# basic-handheld-turbidimeter.net
KiCad netlist of a schematic drawn in EAGLE
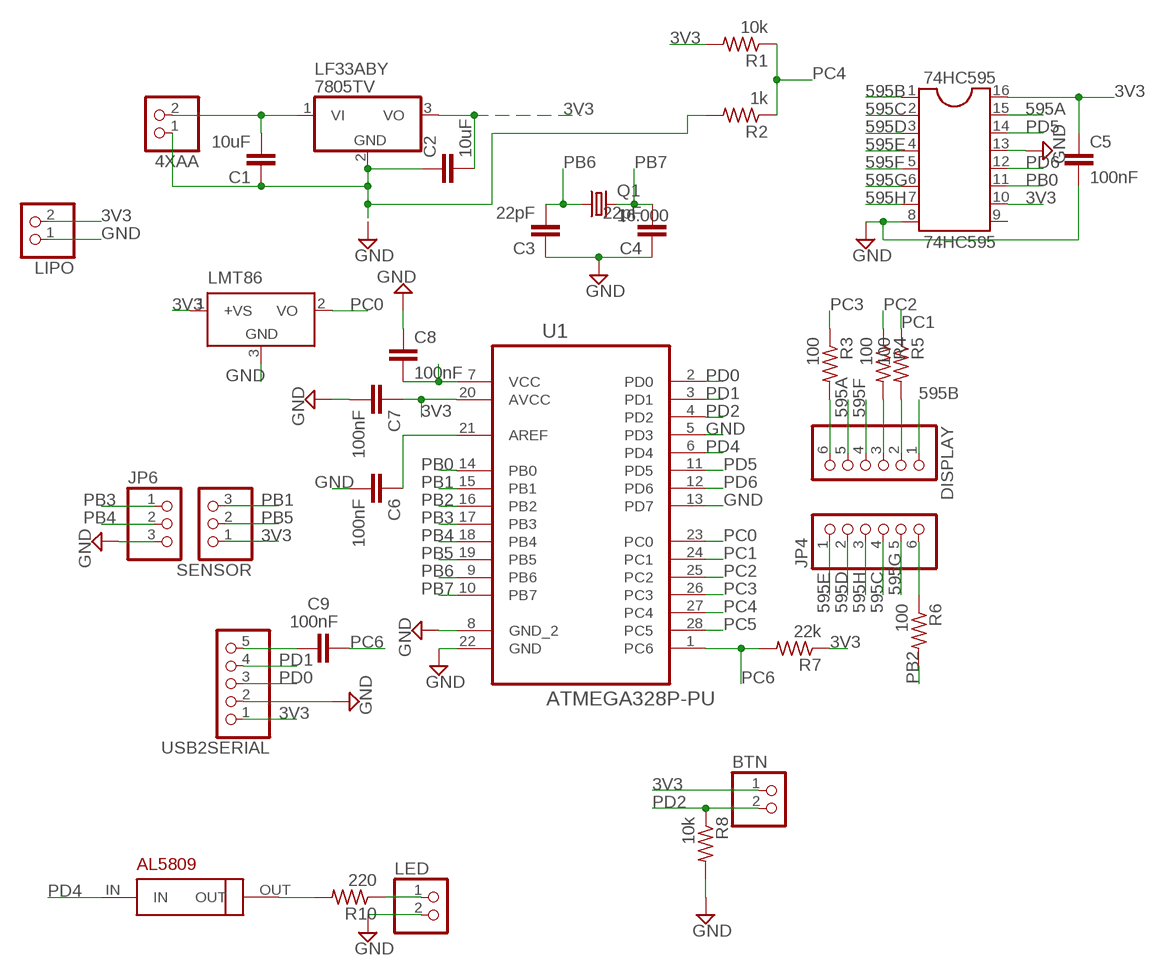
[diagram p0: schematic, sheet 1]

(export (version "E")
  (design (tool "Eeschema 10.0.6"))
  (components
    (comp (ref "4XAA")
      (value "PINHD-1X2")
      (footprint "eagle-import:1X02")
      (libsource (lib "eagle-import") (part "PINHD-1X2"))
    )
    (comp (ref "74HC595")
      (value "74HC595")
      (footprint "eagle-import:DIL16")
      (libsource (lib "eagle-import") (part "DIL16"))
    )
    (comp (ref "BTN")
      (value "PINHD-1X2")
      (footprint "eagle-import:1X02")
      (libsource (lib "eagle-import") (part "PINHD-1X2"))
    )
    (comp (ref "C1")
      (value "10uF")
      (footprint "eagle-import:CAP-PTH-SMALLEZ")
      (libsource (lib "eagle-import") (part "CAPEZ"))
    )
    (comp (ref "C2")
      (value "10uF")
      (footprint "eagle-import:CAP-PTH-SMALLEZ")
      (libsource (lib "eagle-import") (part "CAPEZ"))
    )
    (comp (ref "C3")
      (value "22pF")
      (footprint "eagle-import:CAP-PTH-SMALLEZ")
      (libsource (lib "eagle-import") (part "CAPEZ"))
    )
    (comp (ref "C4")
      (value "22pF")
      (footprint "eagle-import:CAP-PTH-SMALLEZ")
      (libsource (lib "eagle-import") (part "CAPEZ"))
    )
    (comp (ref "C5")
      (value "100nF")
      (footprint "eagle-import:CAP-PTH-SMALLEZ")
      (libsource (lib "eagle-import") (part "CAPEZ"))
    )
    (comp (ref "C6")
      (value "100nF")
      (footprint "eagle-import:CAP-PTH-SMALLEZ")
      (libsource (lib "eagle-import") (part "CAPEZ"))
    )
    (comp (ref "C7")
      (value "100nF")
      (footprint "eagle-import:CAP-PTH-SMALLEZ")
      (libsource (lib "eagle-import") (part "CAPEZ"))
    )
    (comp (ref "C8")
      (value "100nF")
      (footprint "eagle-import:CAP-PTH-SMALLEZ")
      (libsource (lib "eagle-import") (part "CAPEZ"))
    )
    (comp (ref "C9")
      (value "100nF")
      (footprint "eagle-import:CAP-PTH-SMALLEZ")
      (libsource (lib "eagle-import") (part "CAPEZ"))
    )
    (comp (ref "DISPLAY")
      (value "PINHD-1X6")
      (footprint "eagle-import:1X06")
      (libsource (lib "eagle-import") (part "PINHD-1X6"))
    )
    (comp (ref "JP4")
      (value "PINHD-1X6")
      (footprint "eagle-import:1X06")
      (libsource (lib "eagle-import") (part "PINHD-1X6"))
    )
    (comp (ref "JP6")
      (value "PINHD-1X3")
      (footprint "eagle-import:1X03")
      (libsource (lib "eagle-import") (part "PINHD-1X3"))
    )
    (comp (ref "LED")
      (value "PINHD-1X2")
      (footprint "eagle-import:1X02")
      (libsource (lib "eagle-import") (part "PINHD-1X2"))
    )
    (comp (ref "LF33ABY")
      (value "7805TV")
      (footprint "eagle-import:TO220V")
      (libsource (lib "eagle-import") (part "78TV05"))
    )
    (comp (ref "LIPO")
      (value "PINHD-1X2")
      (footprint "eagle-import:1X02")
      (libsource (lib "eagle-import") (part "PINHD-1X2"))
    )
    (comp (ref "LMT86")
      (value "LM35CZ")
      (footprint "eagle-import:TO92")
      (libsource (lib "eagle-import") (part "LM35CZ"))
    )
    (comp (ref "Q1")
      (value "16.000")
      (footprint "eagle-import:HC49_S")
      (libsource (lib "eagle-import") (part "CRYSTALHC49S"))
    )
    (comp (ref "R1")
      (value "10k")
      (footprint "eagle-import:0207_12")
      (libsource (lib "eagle-import") (part "R-US_0207/12"))
    )
    (comp (ref "R2")
      (value "1k")
      (footprint "eagle-import:0207_12")
      (libsource (lib "eagle-import") (part "R-US_0207/12"))
    )
    (comp (ref "R3")
      (value "100")
      (footprint "eagle-import:0207_12")
      (libsource (lib "eagle-import") (part "R-US_0207/12"))
    )
    (comp (ref "R4")
      (value "100")
      (footprint "eagle-import:0207_12")
      (libsource (lib "eagle-import") (part "R-US_0207/12"))
    )
    (comp (ref "R5")
      (value "100")
      (footprint "eagle-import:0207_12")
      (libsource (lib "eagle-import") (part "R-US_0207/12"))
    )
    (comp (ref "R6")
      (value "100")
      (footprint "eagle-import:0207_12")
      (libsource (lib "eagle-import") (part "R-US_0207/12"))
    )
    (comp (ref "R7")
      (value "22k")
      (footprint "eagle-import:0207_12")
      (libsource (lib "eagle-import") (part "R-US_0207/12"))
    )
    (comp (ref "R8")
      (value "10k")
      (footprint "eagle-import:0207_12")
      (libsource (lib "eagle-import") (part "R-US_0207/12"))
    )
    (comp (ref "R10")
      (value "220")
      (footprint "eagle-import:0207_12")
      (libsource (lib "eagle-import") (part "R-US_0207/12"))
    )
    (comp (ref "SENSOR")
      (value "PINHD-1X3")
      (footprint "eagle-import:1X03")
      (libsource (lib "eagle-import") (part "PINHD-1X3"))
    )
    (comp (ref "U$6")
      (value "AL5809")
      (footprint "eagle-import:AL5809")
      (libsource (lib "eagle-import") (part "AL5809"))
    )
    (comp (ref "U1")
      (value "ATMEGA328P-PU")
      (footprint "eagle-import:DIP254P762X457-28")
      (libsource (lib "eagle-import") (part "ATMEGA328P-PU"))
    )
    (comp (ref "USB2SERIAL")
      (value "PINHD-1X5")
      (footprint "eagle-import:1X05")
      (libsource (lib "eagle-import") (part "PINHD-1X5"))
    )
  )
  (nets
    (net (code "1") (name "/3V3") (class "Default")
      (node (ref "74HC595") (pin "10") (pinfunction "10_10") (pintype "passive"))
      (node (ref "74HC595") (pin "16") (pinfunction "16_16") (pintype "passive"))
      (node (ref "BTN") (pin "1") (pinfunction "1_1") (pintype "passive"))
      (node (ref "C2") (pin "2") (pinfunction "2_2") (pintype "passive"))
      (node (ref "C5") (pin "1") (pinfunction "1_1") (pintype "passive"))
      (node (ref "C7") (pin "1") (pinfunction "1_1") (pintype "passive"))
      (node (ref "C8") (pin "2") (pinfunction "2_2") (pintype "passive"))
      (node (ref "LF33ABY") (pin "3") (pinfunction "VO_3") (pintype "passive"))
      (node (ref "LIPO") (pin "2") (pinfunction "2_2") (pintype "passive"))
      (node (ref "LMT86") (pin "1") (pinfunction "+VS_1") (pintype "input"))
      (node (ref "R1") (pin "2") (pinfunction "2_2") (pintype "passive"))
      (node (ref "R7") (pin "1") (pinfunction "1_1") (pintype "passive"))
      (node (ref "SENSOR") (pin "1") (pinfunction "1_1") (pintype "passive"))
      (node (ref "U1") (pin "20") (pinfunction "AVCC_20") (pintype "power_in"))
      (node (ref "U1") (pin "7") (pinfunction "VCC_7") (pintype "power_in"))
      (node (ref "USB2SERIAL") (pin "1") (pinfunction "1_1") (pintype "passive"))
    )
    (net (code "2") (name "/595A") (class "Default")
      (node (ref "74HC595") (pin "15") (pinfunction "15_15") (pintype "passive"))
      (node (ref "DISPLAY") (pin "5") (pinfunction "5_5") (pintype "passive"))
    )
    (net (code "3") (name "/595B") (class "Default")
      (node (ref "74HC595") (pin "1") (pinfunction "1_1") (pintype "passive"))
      (node (ref "DISPLAY") (pin "1") (pinfunction "1_1") (pintype "passive"))
    )
    (net (code "4") (name "/595C") (class "Default")
      (node (ref "74HC595") (pin "2") (pinfunction "2_2") (pintype "passive"))
      (node (ref "JP4") (pin "4") (pinfunction "4_4") (pintype "passive"))
    )
    (net (code "5") (name "/595D") (class "Default")
      (node (ref "74HC595") (pin "3") (pinfunction "3_3") (pintype "passive"))
      (node (ref "JP4") (pin "2") (pinfunction "2_2") (pintype "passive"))
    )
    (net (code "6") (name "/595E") (class "Default")
      (node (ref "74HC595") (pin "4") (pinfunction "4_4") (pintype "passive"))
      (node (ref "JP4") (pin "1") (pinfunction "1_1") (pintype "passive"))
    )
    (net (code "7") (name "/595F") (class "Default")
      (node (ref "74HC595") (pin "5") (pinfunction "5_5") (pintype "passive"))
      (node (ref "DISPLAY") (pin "4") (pinfunction "4_4") (pintype "passive"))
    )
    (net (code "8") (name "/595G") (class "Default")
      (node (ref "74HC595") (pin "6") (pinfunction "6_6") (pintype "passive"))
      (node (ref "JP4") (pin "5") (pinfunction "5_5") (pintype "passive"))
    )
    (net (code "9") (name "/595H") (class "Default")
      (node (ref "74HC595") (pin "7") (pinfunction "7_7") (pintype "passive"))
      (node (ref "JP4") (pin "3") (pinfunction "3_3") (pintype "passive"))
    )
    (net (code "10") (name "/PB0") (class "Default")
      (node (ref "74HC595") (pin "11") (pinfunction "11_11") (pintype "passive"))
      (node (ref "U1") (pin "14") (pinfunction "PB0_14") (pintype "bidirectional"))
    )
    (net (code "11") (name "/PB1") (class "Default")
      (node (ref "SENSOR") (pin "3") (pinfunction "3_3") (pintype "passive"))
      (node (ref "U1") (pin "15") (pinfunction "PB1_15") (pintype "bidirectional"))
    )
    (net (code "12") (name "/PB2") (class "Default")
      (node (ref "R6") (pin "2") (pinfunction "2_2") (pintype "passive"))
      (node (ref "U1") (pin "16") (pinfunction "PB2_16") (pintype "bidirectional"))
    )
    (net (code "13") (name "/PB3") (class "Default")
      (node (ref "JP6") (pin "1") (pinfunction "1_1") (pintype "passive"))
      (node (ref "U1") (pin "17") (pinfunction "PB3_17") (pintype "bidirectional"))
    )
    (net (code "14") (name "/PB4") (class "Default")
      (node (ref "JP6") (pin "2") (pinfunction "2_2") (pintype "passive"))
      (node (ref "U1") (pin "18") (pinfunction "PB4_18") (pintype "bidirectional"))
    )
    (net (code "15") (name "/PB5") (class "Default")
      (node (ref "SENSOR") (pin "2") (pinfunction "2_2") (pintype "passive"))
      (node (ref "U1") (pin "19") (pinfunction "PB5_19") (pintype "bidirectional"))
    )
    (net (code "16") (name "/PB6") (class "Default")
      (node (ref "C3") (pin "2") (pinfunction "2_2") (pintype "passive"))
      (node (ref "Q1") (pin "1") (pinfunction "1_1") (pintype "passive"))
      (node (ref "U1") (pin "9") (pinfunction "PB6_9") (pintype "bidirectional"))
    )
    (net (code "17") (name "/PB7") (class "Default")
      (node (ref "C4") (pin "2") (pinfunction "2_2") (pintype "passive"))
      (node (ref "Q1") (pin "2") (pinfunction "2_2") (pintype "passive"))
      (node (ref "U1") (pin "10") (pinfunction "PB7_10") (pintype "bidirectional"))
    )
    (net (code "18") (name "/PC0") (class "Default")
      (node (ref "LMT86") (pin "2") (pinfunction "VO_2") (pintype "input"))
      (node (ref "U1") (pin "23") (pinfunction "PC0_23") (pintype "bidirectional"))
    )
    (net (code "19") (name "/PC1") (class "Default")
      (node (ref "R5") (pin "1") (pinfunction "1_1") (pintype "passive"))
      (node (ref "U1") (pin "24") (pinfunction "PC1_24") (pintype "bidirectional"))
    )
    (net (code "20") (name "/PC2") (class "Default")
      (node (ref "R4") (pin "1") (pinfunction "1_1") (pintype "passive"))
      (node (ref "U1") (pin "25") (pinfunction "PC2_25") (pintype "bidirectional"))
    )
    (net (code "21") (name "/PC3") (class "Default")
      (node (ref "R3") (pin "1") (pinfunction "1_1") (pintype "passive"))
      (node (ref "U1") (pin "26") (pinfunction "PC3_26") (pintype "bidirectional"))
    )
    (net (code "22") (name "/PC4") (class "Default")
      (node (ref "R1") (pin "1") (pinfunction "1_1") (pintype "passive"))
      (node (ref "R2") (pin "1") (pinfunction "1_1") (pintype "passive"))
      (node (ref "U1") (pin "27") (pinfunction "PC4_27") (pintype "bidirectional"))
    )
    (net (code "23") (name "/PC5") (class "Default")
      (node (ref "U1") (pin "28") (pinfunction "PC5_28") (pintype "bidirectional"))
    )
    (net (code "24") (name "/PC6") (class "Default")
      (node (ref "C9") (pin "1") (pinfunction "1_1") (pintype "passive"))
      (node (ref "R7") (pin "2") (pinfunction "2_2") (pintype "passive"))
      (node (ref "U1") (pin "1") (pinfunction "PC6_1") (pintype "bidirectional"))
    )
    (net (code "25") (name "/PD0") (class "Default")
      (node (ref "U1") (pin "2") (pinfunction "PD0_2") (pintype "bidirectional"))
      (node (ref "USB2SERIAL") (pin "3") (pinfunction "3_3") (pintype "passive"))
    )
    (net (code "26") (name "/PD1") (class "Default")
      (node (ref "U1") (pin "3") (pinfunction "PD1_3") (pintype "bidirectional"))
      (node (ref "USB2SERIAL") (pin "4") (pinfunction "4_4") (pintype "passive"))
    )
    (net (code "27") (name "/PD2") (class "Default")
      (node (ref "BTN") (pin "2") (pinfunction "2_2") (pintype "passive"))
      (node (ref "R8") (pin "1") (pinfunction "1_1") (pintype "passive"))
      (node (ref "U1") (pin "4") (pinfunction "PD2_4") (pintype "bidirectional"))
    )
    (net (code "28") (name "/PD4") (class "Default")
      (node (ref "U$6") (pin "IN") (pinfunction "IN_IN") (pintype "bidirectional"))
      (node (ref "U1") (pin "6") (pinfunction "PD4_6") (pintype "bidirectional"))
    )
    (net (code "29") (name "/PD5") (class "Default")
      (node (ref "74HC595") (pin "14") (pinfunction "14_14") (pintype "passive"))
      (node (ref "U1") (pin "11") (pinfunction "PD5_11") (pintype "bidirectional"))
    )
    (net (code "30") (name "/PD6") (class "Default")
      (node (ref "74HC595") (pin "12") (pinfunction "12_12") (pintype "passive"))
      (node (ref "U1") (pin "12") (pinfunction "PD6_12") (pintype "bidirectional"))
    )
    (net (code "31") (name "GND") (class "Default")
      (node (ref "4XAA") (pin "1") (pinfunction "1_1") (pintype "passive"))
      (node (ref "74HC595") (pin "13") (pinfunction "13_13") (pintype "passive"))
      (node (ref "74HC595") (pin "8") (pinfunction "8_8") (pintype "passive"))
      (node (ref "C1") (pin "1") (pinfunction "1_1") (pintype "passive"))
      (node (ref "C2") (pin "1") (pinfunction "1_1") (pintype "passive"))
      (node (ref "C3") (pin "1") (pinfunction "1_1") (pintype "passive"))
      (node (ref "C4") (pin "1") (pinfunction "1_1") (pintype "passive"))
      (node (ref "C5") (pin "2") (pinfunction "2_2") (pintype "passive"))
      (node (ref "C6") (pin "2") (pinfunction "2_2") (pintype "passive"))
      (node (ref "C7") (pin "2") (pinfunction "2_2") (pintype "passive"))
      (node (ref "C8") (pin "1") (pinfunction "1_1") (pintype "passive"))
      (node (ref "JP6") (pin "3") (pinfunction "3_3") (pintype "passive"))
      (node (ref "LED") (pin "2") (pinfunction "2_2") (pintype "passive"))
      (node (ref "LF33ABY") (pin "2") (pinfunction "GND_2") (pintype "passive"))
      (node (ref "LIPO") (pin "1") (pinfunction "1_1") (pintype "passive"))
      (node (ref "LMT86") (pin "3") (pinfunction "GND_3") (pintype "power_in"))
      (node (ref "R2") (pin "2") (pinfunction "2_2") (pintype "passive"))
      (node (ref "R8") (pin "2") (pinfunction "2_2") (pintype "passive"))
      (node (ref "U1") (pin "13") (pinfunction "PD7_13") (pintype "bidirectional"))
      (node (ref "U1") (pin "22") (pinfunction "GND_22") (pintype "passive"))
      (node (ref "U1") (pin "5") (pinfunction "PD3_5") (pintype "bidirectional"))
      (node (ref "U1") (pin "8") (pinfunction "GND_2_8") (pintype "passive"))
      (node (ref "USB2SERIAL") (pin "2") (pinfunction "2_2") (pintype "passive"))
    )
    (net (code "32") (name "Net-(C9-Pad2)") (class "Default")
      (node (ref "C9") (pin "2") (pinfunction "2_2") (pintype "passive"))
      (node (ref "USB2SERIAL") (pin "5") (pinfunction "5_5") (pintype "passive"))
    )
    (net (code "33") (name "Net-(DISPLAY-Pad2)") (class "Default")
      (node (ref "DISPLAY") (pin "2") (pinfunction "2_2") (pintype "passive"))
      (node (ref "R5") (pin "2") (pinfunction "2_2") (pintype "passive"))
    )
    (net (code "34") (name "Net-(DISPLAY-Pad3)") (class "Default")
      (node (ref "DISPLAY") (pin "3") (pinfunction "3_3") (pintype "passive"))
      (node (ref "R4") (pin "2") (pinfunction "2_2") (pintype "passive"))
    )
    (net (code "35") (name "Net-(DISPLAY-Pad6)") (class "Default")
      (node (ref "DISPLAY") (pin "6") (pinfunction "6_6") (pintype "passive"))
      (node (ref "R3") (pin "2") (pinfunction "2_2") (pintype "passive"))
    )
    (net (code "36") (name "Net-(JP4-Pad6)") (class "Default")
      (node (ref "JP4") (pin "6") (pinfunction "6_6") (pintype "passive"))
      (node (ref "R6") (pin "1") (pinfunction "1_1") (pintype "passive"))
    )
    (net (code "37") (name "Net-(LED-Pad1)") (class "Default")
      (node (ref "LED") (pin "1") (pinfunction "1_1") (pintype "passive"))
      (node (ref "R10") (pin "1") (pinfunction "1_1") (pintype "passive"))
    )
    (net (code "38") (name "Net-(LF33ABY-VI)") (class "Default")
      (node (ref "4XAA") (pin "2") (pinfunction "2_2") (pintype "passive"))
      (node (ref "C1") (pin "2") (pinfunction "2_2") (pintype "passive"))
      (node (ref "LF33ABY") (pin "1") (pinfunction "VI_1") (pintype "input"))
    )
    (net (code "39") (name "Net-(R10-Pad2)") (class "Default")
      (node (ref "R10") (pin "2") (pinfunction "2_2") (pintype "passive"))
      (node (ref "U$6") (pin "OUT") (pinfunction "OUT_OUT") (pintype "bidirectional"))
    )
    (net (code "40") (name "Net-(U1-AREF)") (class "Default")
      (node (ref "C6") (pin "1") (pinfunction "1_1") (pintype "passive"))
      (node (ref "U1") (pin "21") (pinfunction "AREF_21") (pintype "input"))
    )
    (net (code "41") (name "unconnected-(74HC595-Pad9)") (class "Default")
      (node (ref "74HC595") (pin "9") (pinfunction "9_9") (pintype "passive"))
    )
  )
)
